# design.net
KiCad netlist of a schematic drawn in Altium Designer
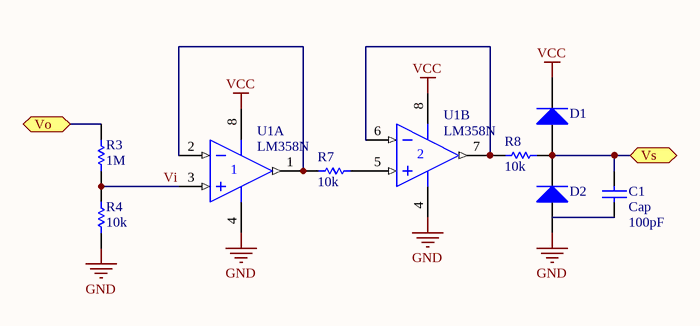
[diagram p0: 调理电路.SchDoc]

(export (version "E")
  (design (tool "Eeschema 10.0.6"))
  (components
    (comp (ref "C1")
      (value "Cap")
      (footprint "RAD-0.3")
      (description "Capacitor")
      (fields (field (name "ALTIUM_VALUE") "100pF") (field (name "PUBLISHER") "Altium Limited"))
      (libsource (lib "Miscellaneous Devices") (part "Cap"))
    )
    (comp (ref "D1")
      (value "~")
      (footprint "SMC")
      (description "Default Diode")
      (fields (field (name "PUBLISHER") "Altium Limited"))
      (libsource (lib "Miscellaneous Devices") (part "Diode"))
    )
    (comp (ref "D2")
      (value "~")
      (footprint "SMC")
      (description "Default Diode")
      (fields (field (name "PUBLISHER") "Altium Limited"))
      (libsource (lib "Miscellaneous Devices") (part "Diode"))
    )
    (comp (ref "R3")
      (value "1M")
      (footprint "AXIAL-0.3")
      (description "Resistor")
      (fields (field (name "PUBLISHER") "Altium Limited"))
      (libsource (lib "Miscellaneous Devices") (part "Res1"))
    )
    (comp (ref "R4")
      (value "10k")
      (footprint "AXIAL-0.3")
      (description "Resistor")
      (fields (field (name "PUBLISHER") "Altium Limited"))
      (libsource (lib "Miscellaneous Devices") (part "Res1"))
    )
    (comp (ref "R7")
      (value "10k")
      (footprint "AXIAL-0.3")
      (description "Resistor")
      (fields (field (name "PUBLISHER") "Altium Limited"))
      (libsource (lib "Miscellaneous Devices") (part "Res1"))
    )
    (comp (ref "R8")
      (value "10k")
      (footprint "AXIAL-0.3")
      (description "Resistor")
      (fields (field (name "PUBLISHER") "Altium Limited"))
      (libsource (lib "Miscellaneous Devices") (part "Res1"))
    )
    (comp (ref "U1")
      (value "LM358N")
      (footprint "626-05")
      (description "Dual Low-Power Operational Amplifier")
      (fields (field (name "PUBLISHER") "Altium Limited"))
      (libsource (lib "Motorola Amplifier Operational Amplifier") (part "LM358N"))
    )
  )
  (nets
    (net (code "1") (name "/Vi") (class "Default")
      (node (ref "R3") (pin "1") (pinfunction "1_1") (pintype "passive"))
      (node (ref "R4") (pin "2") (pinfunction "2_2") (pintype "passive"))
      (node (ref "U1") (pin "3") (pinfunction "IN+_3") (pintype "input"))
    )
    (net (code "2") (name "/Vo") (class "Default")
      (node (ref "R3") (pin "2") (pinfunction "2_2") (pintype "passive"))
    )
    (net (code "3") (name "/Vs") (class "Default")
      (node (ref "C1") (pin "2") (pinfunction "2_2") (pintype "passive"))
      (node (ref "D1") (pin "1") (pinfunction "A_1") (pintype "passive"))
      (node (ref "D2") (pin "2") (pinfunction "K_2") (pintype "passive"))
      (node (ref "R8") (pin "1") (pinfunction "1_1") (pintype "passive"))
    )
    (net (code "4") (name "GND") (class "Default")
      (node (ref "D2") (pin "1") (pinfunction "A_1") (pintype "passive"))
      (node (ref "R4") (pin "1") (pinfunction "1_1") (pintype "passive"))
      (node (ref "U1") (pin "4") (pinfunction "V-_4") (pintype "power_in"))
    )
    (net (code "5") (name "Net-(U1A-IN-)") (class "Default")
      (node (ref "R7") (pin "2") (pinfunction "2_2") (pintype "passive"))
      (node (ref "U1") (pin "1") (pinfunction "OUT_1") (pintype "output"))
      (node (ref "U1") (pin "2") (pinfunction "IN-_2") (pintype "input"))
    )
    (net (code "6") (name "Net-(U1B-IN+)") (class "Default")
      (node (ref "R7") (pin "1") (pinfunction "1_1") (pintype "passive"))
      (node (ref "U1") (pin "5") (pinfunction "IN+_5") (pintype "input"))
    )
    (net (code "7") (name "Net-(U1B-IN-)") (class "Default")
      (node (ref "R8") (pin "2") (pinfunction "2_2") (pintype "passive"))
      (node (ref "U1") (pin "6") (pinfunction "IN-_6") (pintype "input"))
      (node (ref "U1") (pin "7") (pinfunction "OUT_7") (pintype "output"))
    )
    (net (code "8") (name "VCC") (class "Default")
      (node (ref "D1") (pin "2") (pinfunction "K_2") (pintype "passive"))
      (node (ref "U1") (pin "8") (pinfunction "V+_8") (pintype "power_in"))
    )
    (net (code "9") (name "unconnected-(C1-Pad1)") (class "Default")
      (node (ref "C1") (pin "1") (pinfunction "1_1") (pintype "passive"))
    )
  )
)
